# Automaton_no_switches.net
KiCad netlist of a schematic drawn in EAGLE
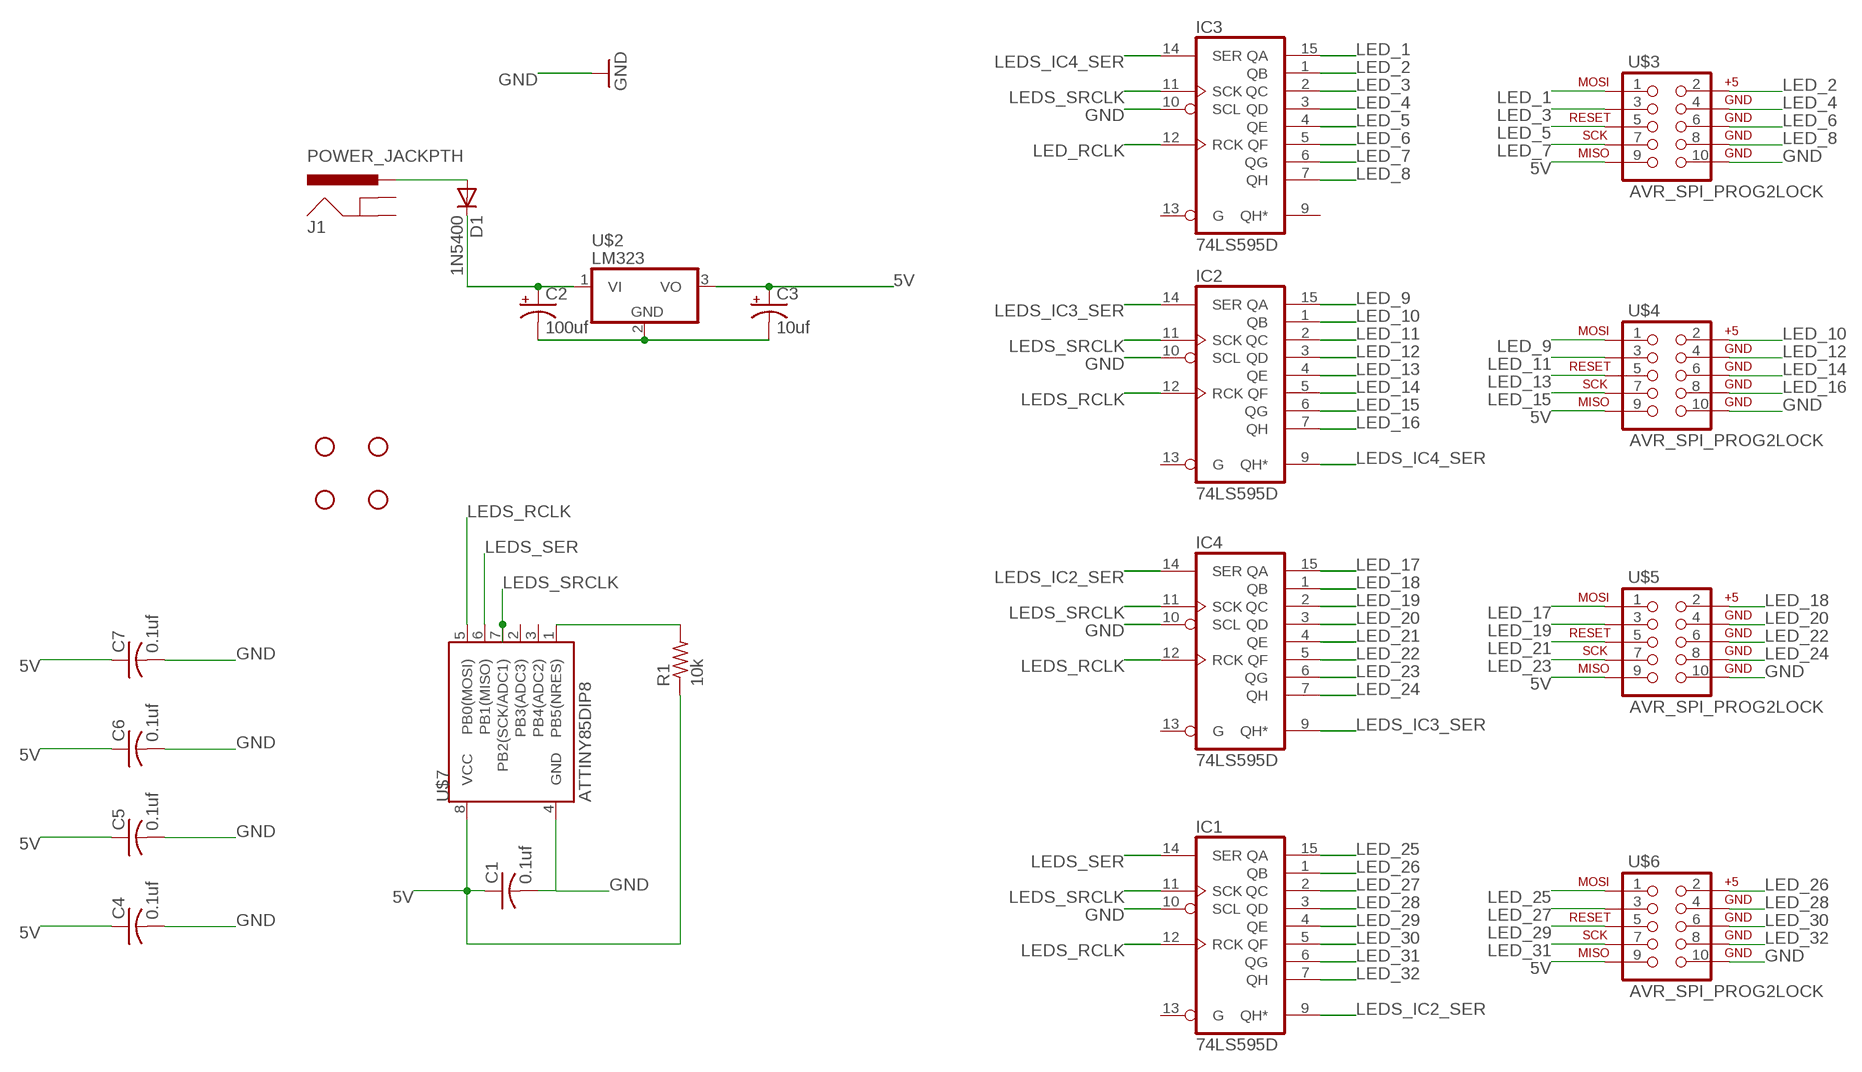
[diagram p0: schematic, sheet 1]

(export (version "E")
  (design (tool "Eeschema 10.0.6"))
  (components
    (comp (ref "C1")
      (value "0.1uf")
      (footprint "eagle-import:C025-024X044")
      (libsource (lib "eagle-import") (part "C-US025-024X044"))
    )
    (comp (ref "C2")
      (value "100uf")
      (footprint "eagle-import:E5-10,5")
      (libsource (lib "eagle-import") (part "CPOL-USE5-10.5"))
    )
    (comp (ref "C3")
      (value "10uf")
      (footprint "eagle-import:E2-5")
      (libsource (lib "eagle-import") (part "CPOL-USE2-5"))
    )
    (comp (ref "C4")
      (value "0.1uf")
      (footprint "eagle-import:C025-024X044")
      (libsource (lib "eagle-import") (part "C-US025-024X044"))
    )
    (comp (ref "C5")
      (value "0.1uf")
      (footprint "eagle-import:C025-024X044")
      (libsource (lib "eagle-import") (part "C-US025-024X044"))
    )
    (comp (ref "C6")
      (value "0.1uf")
      (footprint "eagle-import:C025-024X044")
      (libsource (lib "eagle-import") (part "C-US025-024X044"))
    )
    (comp (ref "C7")
      (value "0.1uf")
      (footprint "eagle-import:C025-024X044")
      (libsource (lib "eagle-import") (part "C-US025-024X044"))
    )
    (comp (ref "D1")
      (value "1N5400")
      (footprint "eagle-import:DO201-15")
      (libsource (lib "eagle-import") (part "1N5400"))
    )
    (comp (ref "IC1")
      (value "74LS595D")
      (footprint "eagle-import:SO16")
      (libsource (lib "eagle-import") (part "74595DLS"))
    )
    (comp (ref "IC2")
      (value "74LS595D")
      (footprint "eagle-import:SO16")
      (libsource (lib "eagle-import") (part "74595DLS"))
    )
    (comp (ref "IC3")
      (value "74LS595D")
      (footprint "eagle-import:SO16")
      (libsource (lib "eagle-import") (part "74595DLS"))
    )
    (comp (ref "IC4")
      (value "74LS595D")
      (footprint "eagle-import:SO16")
      (libsource (lib "eagle-import") (part "74595DLS"))
    )
    (comp (ref "J1")
      (value "POWER_JACKPTH")
      (footprint "eagle-import:POWER_JACK_PTH")
      (libsource (lib "eagle-import") (part "POWER_JACKPTH"))
    )
    (comp (ref "JP1")
      (value "STAND-OFF")
      (footprint "eagle-import:STAND-OFF")
      (libsource (lib "eagle-import") (part "STAND-OFF"))
    )
    (comp (ref "JP2")
      (value "STAND-OFF")
      (footprint "eagle-import:STAND-OFF")
      (libsource (lib "eagle-import") (part "STAND-OFF"))
    )
    (comp (ref "JP3")
      (value "STAND-OFF")
      (footprint "eagle-import:STAND-OFF")
      (libsource (lib "eagle-import") (part "STAND-OFF"))
    )
    (comp (ref "JP4")
      (value "STAND-OFF")
      (footprint "eagle-import:STAND-OFF")
      (libsource (lib "eagle-import") (part "STAND-OFF"))
    )
    (comp (ref "R1")
      (value "10k")
      (footprint "eagle-import:M1206")
      (libsource (lib "eagle-import") (part "R-US_M1206"))
    )
    (comp (ref "U$2")
      (value "LM323")
      (footprint "eagle-import:TO220H")
      (libsource (lib "eagle-import") (part "LM323"))
    )
    (comp (ref "U$3")
      (value "AVR_SPI_PROG2LOCK")
      (footprint "eagle-import:2X5-SHROUDED_LOCK")
      (libsource (lib "eagle-import") (part "AVR_SPI_PROG2LOCK"))
    )
    (comp (ref "U$4")
      (value "AVR_SPI_PROG2LOCK")
      (footprint "eagle-import:2X5-SHROUDED_LOCK")
      (libsource (lib "eagle-import") (part "AVR_SPI_PROG2LOCK"))
    )
    (comp (ref "U$5")
      (value "AVR_SPI_PROG2LOCK")
      (footprint "eagle-import:2X5-SHROUDED_LOCK")
      (libsource (lib "eagle-import") (part "AVR_SPI_PROG2LOCK"))
    )
    (comp (ref "U$6")
      (value "AVR_SPI_PROG2LOCK")
      (footprint "eagle-import:2X5-SHROUDED_LOCK")
      (libsource (lib "eagle-import") (part "AVR_SPI_PROG2LOCK"))
    )
    (comp (ref "U$7")
      (value "ATTINY85DIP8")
      (footprint "eagle-import:DIP08")
      (libsource (lib "eagle-import") (part "ATTINY85DIP8"))
    )
  )
  (nets
    (net (code "1") (name "/5V") (class "Default")
      (node (ref "C1") (pin "1") (pinfunction "1_1") (pintype "passive"))
      (node (ref "C3") (pin "+") (pinfunction "+_+") (pintype "passive"))
      (node (ref "C4") (pin "1") (pinfunction "1_1") (pintype "passive"))
      (node (ref "C5") (pin "1") (pinfunction "1_1") (pintype "passive"))
      (node (ref "C6") (pin "1") (pinfunction "1_1") (pintype "passive"))
      (node (ref "C7") (pin "1") (pinfunction "1_1") (pintype "passive"))
      (node (ref "R1") (pin "1") (pinfunction "1_1") (pintype "passive"))
      (node (ref "U$2") (pin "3") (pinfunction "VO_3") (pintype "passive"))
      (node (ref "U$3") (pin "9") (pinfunction "9_9") (pintype "passive"))
      (node (ref "U$4") (pin "9") (pinfunction "9_9") (pintype "passive"))
      (node (ref "U$5") (pin "9") (pinfunction "9_9") (pintype "passive"))
      (node (ref "U$6") (pin "9") (pinfunction "9_9") (pintype "passive"))
      (node (ref "U$7") (pin "8") (pinfunction "VCC_8") (pintype "bidirectional"))
    )
    (net (code "2") (name "/LEDS_IC2_SER") (class "Default")
      (node (ref "IC1") (pin "9") (pinfunction "QH*_9") (pintype "tri_state"))
      (node (ref "IC4") (pin "14") (pinfunction "SER_14") (pintype "input"))
    )
    (net (code "3") (name "/LEDS_IC3_SER") (class "Default")
      (node (ref "IC2") (pin "14") (pinfunction "SER_14") (pintype "input"))
      (node (ref "IC4") (pin "9") (pinfunction "QH*_9") (pintype "tri_state"))
    )
    (net (code "4") (name "/LEDS_IC4_SER") (class "Default")
      (node (ref "IC2") (pin "9") (pinfunction "QH*_9") (pintype "tri_state"))
      (node (ref "IC3") (pin "14") (pinfunction "SER_14") (pintype "input"))
    )
    (net (code "5") (name "/LEDS_RCLK") (class "Default")
      (node (ref "IC1") (pin "12") (pinfunction "RCK_12") (pintype "input"))
      (node (ref "IC2") (pin "12") (pinfunction "RCK_12") (pintype "input"))
      (node (ref "IC4") (pin "12") (pinfunction "RCK_12") (pintype "input"))
      (node (ref "U$7") (pin "5") (pinfunction "PB0(MOSI)_5") (pintype "bidirectional"))
    )
    (net (code "6") (name "/LEDS_SER") (class "Default")
      (node (ref "IC1") (pin "14") (pinfunction "SER_14") (pintype "input"))
      (node (ref "U$7") (pin "6") (pinfunction "PB1(MISO)_6") (pintype "bidirectional"))
    )
    (net (code "7") (name "/LEDS_SRCLK") (class "Default")
      (node (ref "IC1") (pin "11") (pinfunction "SCK_11") (pintype "input"))
      (node (ref "IC2") (pin "11") (pinfunction "SCK_11") (pintype "input"))
      (node (ref "IC3") (pin "11") (pinfunction "SCK_11") (pintype "input"))
      (node (ref "IC4") (pin "11") (pinfunction "SCK_11") (pintype "input"))
      (node (ref "U$7") (pin "7") (pinfunction "PB2(SCK/ADC1)_7") (pintype "bidirectional"))
    )
    (net (code "8") (name "/LED_1") (class "Default")
      (node (ref "IC3") (pin "15") (pinfunction "QA_15") (pintype "tri_state"))
      (node (ref "U$3") (pin "1") (pinfunction "1_1") (pintype "passive"))
    )
    (net (code "9") (name "/LED_2") (class "Default")
      (node (ref "IC3") (pin "1") (pinfunction "QB_1") (pintype "tri_state"))
      (node (ref "U$3") (pin "2") (pinfunction "2_2") (pintype "passive"))
    )
    (net (code "10") (name "/LED_3") (class "Default")
      (node (ref "IC3") (pin "2") (pinfunction "QC_2") (pintype "tri_state"))
      (node (ref "U$3") (pin "3") (pinfunction "3_3") (pintype "passive"))
    )
    (net (code "11") (name "/LED_4") (class "Default")
      (node (ref "IC3") (pin "3") (pinfunction "QD_3") (pintype "tri_state"))
      (node (ref "U$3") (pin "4") (pinfunction "4_4") (pintype "passive"))
    )
    (net (code "12") (name "/LED_5") (class "Default")
      (node (ref "IC3") (pin "4") (pinfunction "QE_4") (pintype "tri_state"))
      (node (ref "U$3") (pin "5") (pinfunction "5_5") (pintype "passive"))
    )
    (net (code "13") (name "/LED_6") (class "Default")
      (node (ref "IC3") (pin "5") (pinfunction "QF_5") (pintype "tri_state"))
      (node (ref "U$3") (pin "6") (pinfunction "6_6") (pintype "passive"))
    )
    (net (code "14") (name "/LED_7") (class "Default")
      (node (ref "IC3") (pin "6") (pinfunction "QG_6") (pintype "tri_state"))
      (node (ref "U$3") (pin "7") (pinfunction "7_7") (pintype "passive"))
    )
    (net (code "15") (name "/LED_8") (class "Default")
      (node (ref "IC3") (pin "7") (pinfunction "QH_7") (pintype "tri_state"))
      (node (ref "U$3") (pin "8") (pinfunction "8_8") (pintype "passive"))
    )
    (net (code "16") (name "/LED_9") (class "Default")
      (node (ref "IC2") (pin "15") (pinfunction "QA_15") (pintype "tri_state"))
      (node (ref "U$4") (pin "1") (pinfunction "1_1") (pintype "passive"))
    )
    (net (code "17") (name "/LED_10") (class "Default")
      (node (ref "IC2") (pin "1") (pinfunction "QB_1") (pintype "tri_state"))
      (node (ref "U$4") (pin "2") (pinfunction "2_2") (pintype "passive"))
    )
    (net (code "18") (name "/LED_11") (class "Default")
      (node (ref "IC2") (pin "2") (pinfunction "QC_2") (pintype "tri_state"))
      (node (ref "U$4") (pin "3") (pinfunction "3_3") (pintype "passive"))
    )
    (net (code "19") (name "/LED_12") (class "Default")
      (node (ref "IC2") (pin "3") (pinfunction "QD_3") (pintype "tri_state"))
      (node (ref "U$4") (pin "4") (pinfunction "4_4") (pintype "passive"))
    )
    (net (code "20") (name "/LED_13") (class "Default")
      (node (ref "IC2") (pin "4") (pinfunction "QE_4") (pintype "tri_state"))
      (node (ref "U$4") (pin "5") (pinfunction "5_5") (pintype "passive"))
    )
    (net (code "21") (name "/LED_14") (class "Default")
      (node (ref "IC2") (pin "5") (pinfunction "QF_5") (pintype "tri_state"))
      (node (ref "U$4") (pin "6") (pinfunction "6_6") (pintype "passive"))
    )
    (net (code "22") (name "/LED_15") (class "Default")
      (node (ref "IC2") (pin "6") (pinfunction "QG_6") (pintype "tri_state"))
      (node (ref "U$4") (pin "7") (pinfunction "7_7") (pintype "passive"))
    )
    (net (code "23") (name "/LED_16") (class "Default")
      (node (ref "IC2") (pin "7") (pinfunction "QH_7") (pintype "tri_state"))
      (node (ref "U$4") (pin "8") (pinfunction "8_8") (pintype "passive"))
    )
    (net (code "24") (name "/LED_17") (class "Default")
      (node (ref "IC4") (pin "15") (pinfunction "QA_15") (pintype "tri_state"))
      (node (ref "U$5") (pin "1") (pinfunction "1_1") (pintype "passive"))
    )
    (net (code "25") (name "/LED_18") (class "Default")
      (node (ref "IC4") (pin "1") (pinfunction "QB_1") (pintype "tri_state"))
      (node (ref "U$5") (pin "2") (pinfunction "2_2") (pintype "passive"))
    )
    (net (code "26") (name "/LED_19") (class "Default")
      (node (ref "IC4") (pin "2") (pinfunction "QC_2") (pintype "tri_state"))
      (node (ref "U$5") (pin "3") (pinfunction "3_3") (pintype "passive"))
    )
    (net (code "27") (name "/LED_20") (class "Default")
      (node (ref "IC4") (pin "3") (pinfunction "QD_3") (pintype "tri_state"))
      (node (ref "U$5") (pin "4") (pinfunction "4_4") (pintype "passive"))
    )
    (net (code "28") (name "/LED_21") (class "Default")
      (node (ref "IC4") (pin "4") (pinfunction "QE_4") (pintype "tri_state"))
      (node (ref "U$5") (pin "5") (pinfunction "5_5") (pintype "passive"))
    )
    (net (code "29") (name "/LED_22") (class "Default")
      (node (ref "IC4") (pin "5") (pinfunction "QF_5") (pintype "tri_state"))
      (node (ref "U$5") (pin "6") (pinfunction "6_6") (pintype "passive"))
    )
    (net (code "30") (name "/LED_23") (class "Default")
      (node (ref "IC4") (pin "6") (pinfunction "QG_6") (pintype "tri_state"))
      (node (ref "U$5") (pin "7") (pinfunction "7_7") (pintype "passive"))
    )
    (net (code "31") (name "/LED_24") (class "Default")
      (node (ref "IC4") (pin "7") (pinfunction "QH_7") (pintype "tri_state"))
      (node (ref "U$5") (pin "8") (pinfunction "8_8") (pintype "passive"))
    )
    (net (code "32") (name "/LED_25") (class "Default")
      (node (ref "IC1") (pin "15") (pinfunction "QA_15") (pintype "tri_state"))
      (node (ref "U$6") (pin "1") (pinfunction "1_1") (pintype "passive"))
    )
    (net (code "33") (name "/LED_26") (class "Default")
      (node (ref "IC1") (pin "1") (pinfunction "QB_1") (pintype "tri_state"))
      (node (ref "U$6") (pin "2") (pinfunction "2_2") (pintype "passive"))
    )
    (net (code "34") (name "/LED_27") (class "Default")
      (node (ref "IC1") (pin "2") (pinfunction "QC_2") (pintype "tri_state"))
      (node (ref "U$6") (pin "3") (pinfunction "3_3") (pintype "passive"))
    )
    (net (code "35") (name "/LED_28") (class "Default")
      (node (ref "IC1") (pin "3") (pinfunction "QD_3") (pintype "tri_state"))
      (node (ref "U$6") (pin "4") (pinfunction "4_4") (pintype "passive"))
    )
    (net (code "36") (name "/LED_29") (class "Default")
      (node (ref "IC1") (pin "4") (pinfunction "QE_4") (pintype "tri_state"))
      (node (ref "U$6") (pin "5") (pinfunction "5_5") (pintype "passive"))
    )
    (net (code "37") (name "/LED_30") (class "Default")
      (node (ref "IC1") (pin "5") (pinfunction "QF_5") (pintype "tri_state"))
      (node (ref "U$6") (pin "6") (pinfunction "6_6") (pintype "passive"))
    )
    (net (code "38") (name "/LED_31") (class "Default")
      (node (ref "IC1") (pin "6") (pinfunction "QG_6") (pintype "tri_state"))
      (node (ref "U$6") (pin "7") (pinfunction "7_7") (pintype "passive"))
    )
    (net (code "39") (name "/LED_32") (class "Default")
      (node (ref "IC1") (pin "7") (pinfunction "QH_7") (pintype "tri_state"))
      (node (ref "U$6") (pin "8") (pinfunction "8_8") (pintype "passive"))
    )
    (net (code "40") (name "/LED_RCLK") (class "Default")
      (node (ref "IC3") (pin "12") (pinfunction "RCK_12") (pintype "input"))
    )
    (net (code "41") (name "GND") (class "Default")
      (node (ref "C1") (pin "2") (pinfunction "2_2") (pintype "passive"))
      (node (ref "C4") (pin "2") (pinfunction "2_2") (pintype "passive"))
      (node (ref "C5") (pin "2") (pinfunction "2_2") (pintype "passive"))
      (node (ref "C6") (pin "2") (pinfunction "2_2") (pintype "passive"))
      (node (ref "C7") (pin "2") (pinfunction "2_2") (pintype "passive"))
      (node (ref "IC1") (pin "10") (pinfunction "SCL_10") (pintype "input"))
      (node (ref "IC2") (pin "10") (pinfunction "SCL_10") (pintype "input"))
      (node (ref "IC3") (pin "10") (pinfunction "SCL_10") (pintype "input"))
      (node (ref "IC4") (pin "10") (pinfunction "SCL_10") (pintype "input"))
      (node (ref "U$3") (pin "10") (pinfunction "10_10") (pintype "passive"))
      (node (ref "U$4") (pin "10") (pinfunction "10_10") (pintype "passive"))
      (node (ref "U$5") (pin "10") (pinfunction "10_10") (pintype "passive"))
      (node (ref "U$6") (pin "10") (pinfunction "10_10") (pintype "passive"))
      (node (ref "U$7") (pin "4") (pinfunction "GND_4") (pintype "bidirectional"))
    )
    (net (code "42") (name "Net-(D1-PadA)") (class "Default")
      (node (ref "D1") (pin "A") (pinfunction "A_A") (pintype "passive"))
      (node (ref "J1") (pin "PWR") (pinfunction "PWR_PWR") (pintype "bidirectional"))
    )
    (net (code "43") (name "Net-(U$2-GND)") (class "Default")
      (node (ref "C2") (pin "-") (pinfunction "-_-") (pintype "passive"))
      (node (ref "C3") (pin "-") (pinfunction "-_-") (pintype "passive"))
      (node (ref "U$2") (pin "2") (pinfunction "GND_2") (pintype "passive"))
    )
    (net (code "44") (name "Net-(U$2-VI)") (class "Default")
      (node (ref "C2") (pin "+") (pinfunction "+_+") (pintype "passive"))
      (node (ref "D1") (pin "C") (pinfunction "C_C") (pintype "passive"))
      (node (ref "U$2") (pin "1") (pinfunction "VI_1") (pintype "input"))
    )
    (net (code "45") (name "Net-(U$7-PB5(NRES))") (class "Default")
      (node (ref "R1") (pin "2") (pinfunction "2_2") (pintype "passive"))
      (node (ref "U$7") (pin "1") (pinfunction "PB5(NRES)_1") (pintype "bidirectional"))
    )
    (net (code "46") (name "unconnected-(IC1A-G-Pad13)") (class "Default")
      (node (ref "IC1") (pin "13") (pinfunction "G_13") (pintype "input"))
    )
    (net (code "47") (name "unconnected-(IC2A-G-Pad13)") (class "Default")
      (node (ref "IC2") (pin "13") (pinfunction "G_13") (pintype "input"))
    )
    (net (code "48") (name "unconnected-(IC3A-G-Pad13)") (class "Default")
      (node (ref "IC3") (pin "13") (pinfunction "G_13") (pintype "input"))
    )
    (net (code "49") (name "unconnected-(IC3A-QH*-Pad9)") (class "Default")
      (node (ref "IC3") (pin "9") (pinfunction "QH*_9") (pintype "tri_state"))
    )
    (net (code "50") (name "unconnected-(IC4A-G-Pad13)") (class "Default")
      (node (ref "IC4") (pin "13") (pinfunction "G_13") (pintype "input"))
    )
    (net (code "51") (name "unconnected-(J1-PadGND)") (class "Default")
      (node (ref "J1") (pin "GND") (pinfunction "GND_GND") (pintype "bidirectional"))
    )
    (net (code "52") (name "unconnected-(J1-PadGNDBREAK)") (class "Default")
      (node (ref "J1") (pin "GNDBREAK") (pinfunction "GNDBREAK_GNDBREAK") (pintype "bidirectional"))
    )
    (net (code "53") (name "unconnected-(U$7-PB3(ADC3)-Pad2)") (class "Default")
      (node (ref "U$7") (pin "2") (pinfunction "PB3(ADC3)_2") (pintype "bidirectional"))
    )
    (net (code "54") (name "unconnected-(U$7-PB4(ADC2)-Pad3)") (class "Default")
      (node (ref "U$7") (pin "3") (pinfunction "PB4(ADC2)_3") (pintype "bidirectional"))
    )
  )
)
